# Feeder.net
KiCad netlist of a schematic drawn in Altium Designer
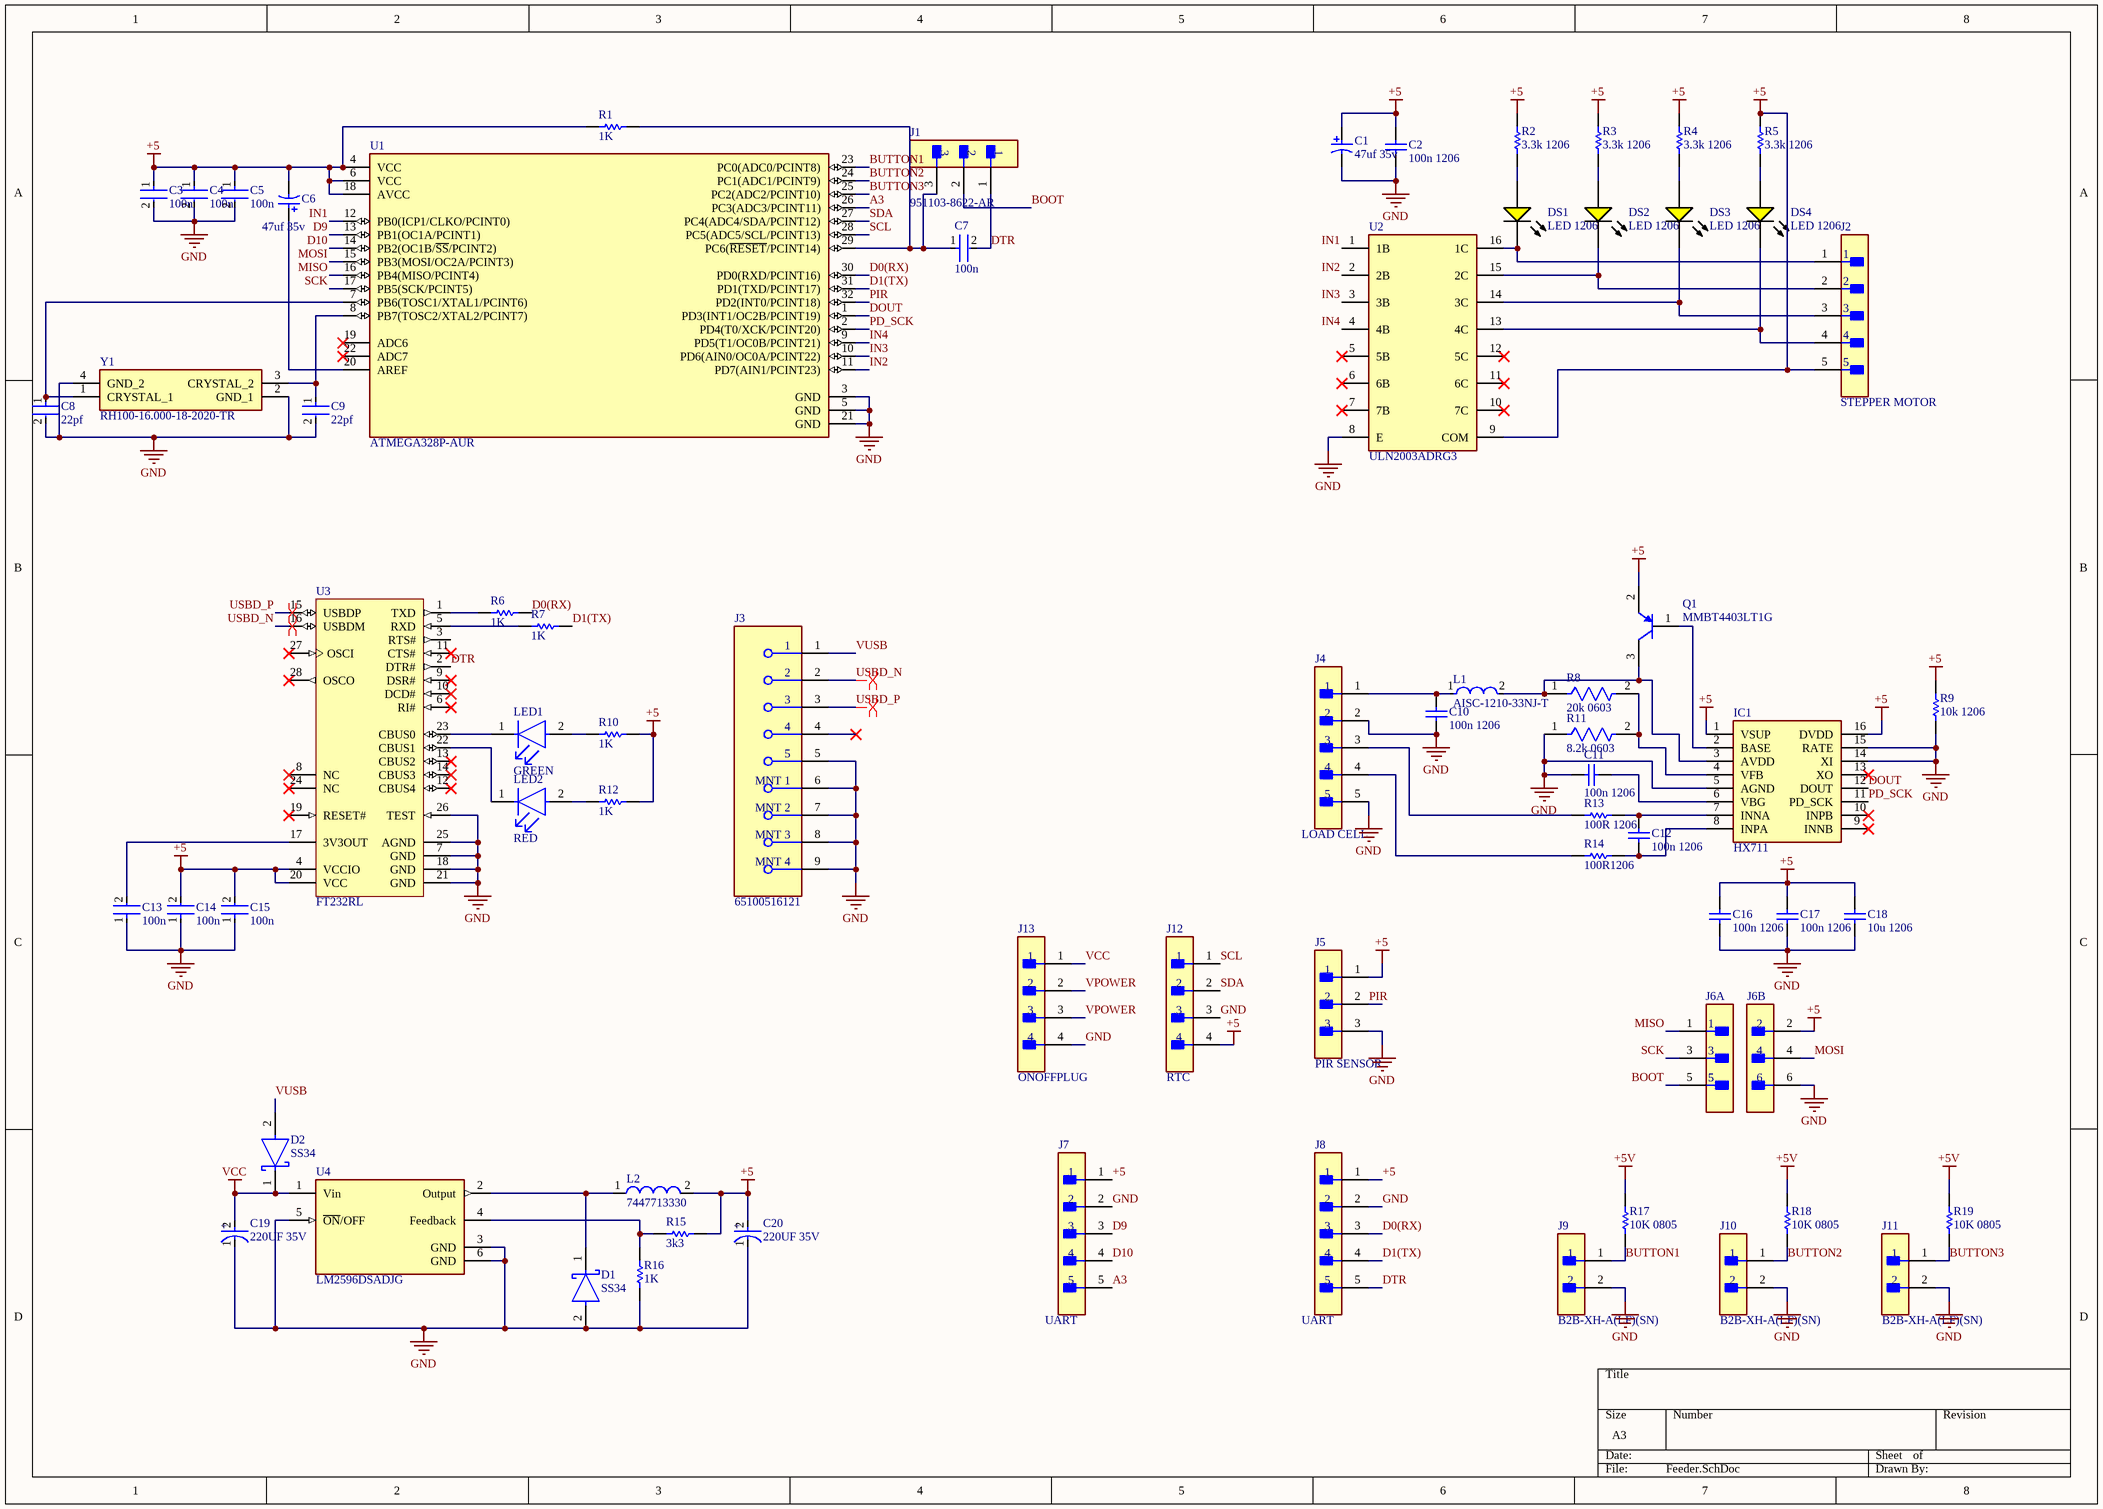
[diagram p0: Feeder.SchDoc]

(export (version "E")
  (design (tool "Eeschema 10.0.6"))
  (components
    (comp (ref "C1")
      (value "47uf 35v")
      (footprint "NIC-CAPA2-6.3X5.8_V")
      (fields (field (name "MANUFACTURER") "Nichicon") (field (name "PARTNUMBER") "UUD1V470MCL1GS"))
      (libsource (lib "Altium Content Vault") (part "NIC-CAP-P-2"))
    )
    (comp (ref "C2")
      (value "100n 1206")
      (footprint "CAPC3216X190X55ML30T25")
      (description "Chip Capacitor, 100 uF, +/- 20%, 6.3 V, -55 to 85 degC, 1206 (3216 Metric), RoHS, Tape and Reel")
      (fields (field (name "TOLERANCE") "20%") (field (name "PARTNUMBER") "GRM31CR60J107ME39L"))
      (libsource (lib "Altium Content Vault") (part "CAP-NP-2"))
    )
    (comp (ref "C3")
      (value "100n")
      (footprint "FP-C1206C-EB-MFG")
      (description "CAP CER 0.1UF 25V 5% NP0 1206")
      (fields
        (field (name "TOLERANCE") "0.05")
        (field (name "OCTOPART") "https://octopart.com/c1206c104j3gactu-kemet-9145095")
      )
      (libsource (lib "Altium Content Vault") (part "b4654b650e69147ec39a6b967a45e02"))
    )
    (comp (ref "C4")
      (value "100n")
      (footprint "FP-C1206C-EB-MFG")
      (description "CAP CER 0.1UF 25V 5% NP0 1206")
      (fields
        (field (name "TOLERANCE") "0.05")
        (field (name "OCTOPART") "https://octopart.com/c1206c104j3gactu-kemet-9145095")
      )
      (libsource (lib "Altium Content Vault") (part "b4654b650e69147ec39a6b967a45e02"))
    )
    (comp (ref "C5")
      (value "100n")
      (footprint "FP-C1206C-EB-MFG")
      (description "CAP CER 0.1UF 25V 5% NP0 1206")
      (fields
        (field (name "TOLERANCE") "0.05")
        (field (name "OCTOPART") "https://octopart.com/c1206c104j3gactu-kemet-9145095")
      )
      (libsource (lib "Altium Content Vault") (part "b4654b650e69147ec39a6b967a45e02"))
    )
    (comp (ref "C6")
      (value "47uf 35v")
      (footprint "NIC-CAPA2-6.3X5.8_V")
      (fields (field (name "MANUFACTURER") "Nichicon") (field (name "PARTNUMBER") "UUD1V470MCL1GS"))
      (libsource (lib "Altium Content Vault") (part "NIC-CAP-P-2"))
    )
    (comp (ref "C7")
      (value "100n")
      (footprint "FP-C1206C-EB-MFG")
      (description "CAP CER 0.1UF 25V 5% NP0 1206")
      (fields
        (field (name "TOLERANCE") "0.05")
        (field (name "OCTOPART") "https://octopart.com/c1206c104j3gactu-kemet-9145095")
      )
      (libsource (lib "Altium Content Vault") (part "b4654b650e69147ec39a6b967a45e02"))
    )
    (comp (ref "C8")
      (value "22pf")
      (footprint "FP-C1206C-EB-MFG")
      (description "1206 22pF Ceramic Multilayer Capacitor; 50VDC; 125degC; C0G Dielec; +/-5% SMD")
      (fields
        (field (name "OCTOPART") "https://octopart.com/c1206c220j5gactu-kemet-131912")
        (field (name "TOLERANCE") "0.05")
      )
      (libsource (lib "Altium Content Vault") (part "b4654b650e69147ec39a6b967a45e02"))
    )
    (comp (ref "C9")
      (value "22pf")
      (footprint "FP-C1206C-EB-MFG")
      (description "1206 22pF Ceramic Multilayer Capacitor; 50VDC; 125degC; C0G Dielec; +/-5% SMD")
      (fields
        (field (name "OCTOPART") "https://octopart.com/c1206c220j5gactu-kemet-131912")
        (field (name "TOLERANCE") "0.05")
      )
      (libsource (lib "Altium Content Vault") (part "b4654b650e69147ec39a6b967a45e02"))
    )
    (comp (ref "C10")
      (value "100n 1206")
      (footprint "CAPC3216X190X55ML30T25")
      (description "Chip Capacitor, 100 uF, +/- 20%, 6.3 V, -55 to 85 degC, 1206 (3216 Metric), RoHS, Tape and Reel")
      (fields (field (name "TOLERANCE") "20%") (field (name "PARTNUMBER") "GRM31CR60J107ME39L"))
      (libsource (lib "Altium Content Vault") (part "CAP-NP-2"))
    )
    (comp (ref "C11")
      (value "100n 1206")
      (footprint "CAPC3216X190X55ML30T25")
      (description "Chip Capacitor, 100 uF, +/- 20%, 6.3 V, -55 to 85 degC, 1206 (3216 Metric), RoHS, Tape and Reel")
      (fields (field (name "TOLERANCE") "20%") (field (name "PARTNUMBER") "GRM31CR60J107ME39L"))
      (libsource (lib "Altium Content Vault") (part "CAP-NP-2"))
    )
    (comp (ref "C12")
      (value "100n 1206")
      (footprint "CAPC3216X190X55ML30T25")
      (description "Chip Capacitor, 100 uF, +/- 20%, 6.3 V, -55 to 85 degC, 1206 (3216 Metric), RoHS, Tape and Reel")
      (fields (field (name "TOLERANCE") "20%") (field (name "PARTNUMBER") "GRM31CR60J107ME39L"))
      (libsource (lib "Altium Content Vault") (part "CAP-NP-2"))
    )
    (comp (ref "C13")
      (value "100n")
      (footprint "FP-C1206C-EB-MFG")
      (description "CAP CER 0.1UF 25V 5% NP0 1206")
      (fields
        (field (name "TOLERANCE") "0.05")
        (field (name "OCTOPART") "https://octopart.com/c1206c104j3gactu-kemet-9145095")
      )
      (libsource (lib "Altium Content Vault") (part "b4654b650e69147ec39a6b967a45e02"))
    )
    (comp (ref "C14")
      (value "100n")
      (footprint "FP-C1206C-EB-MFG")
      (description "CAP CER 0.1UF 25V 5% NP0 1206")
      (fields
        (field (name "TOLERANCE") "0.05")
        (field (name "OCTOPART") "https://octopart.com/c1206c104j3gactu-kemet-9145095")
      )
      (libsource (lib "Altium Content Vault") (part "b4654b650e69147ec39a6b967a45e02"))
    )
    (comp (ref "C15")
      (value "100n")
      (footprint "FP-C1206C-EB-MFG")
      (description "CAP CER 0.1UF 25V 5% NP0 1206")
      (fields
        (field (name "TOLERANCE") "0.05")
        (field (name "OCTOPART") "https://octopart.com/c1206c104j3gactu-kemet-9145095")
      )
      (libsource (lib "Altium Content Vault") (part "b4654b650e69147ec39a6b967a45e02"))
    )
    (comp (ref "C16")
      (value "100n 1206")
      (footprint "CAPC3216X190X55ML30T25")
      (description "Chip Capacitor, 100 uF, +/- 20%, 6.3 V, -55 to 85 degC, 1206 (3216 Metric), RoHS, Tape and Reel")
      (fields (field (name "TOLERANCE") "20%") (field (name "PARTNUMBER") "GRM31CR60J107ME39L"))
      (libsource (lib "Altium Content Vault") (part "CAP-NP-2"))
    )
    (comp (ref "C17")
      (value "100n 1206")
      (footprint "CAPC3216X190X55ML30T25")
      (description "Chip Capacitor, 100 uF, +/- 20%, 6.3 V, -55 to 85 degC, 1206 (3216 Metric), RoHS, Tape and Reel")
      (fields (field (name "TOLERANCE") "20%") (field (name "PARTNUMBER") "GRM31CR60J107ME39L"))
      (libsource (lib "Altium Content Vault") (part "CAP-NP-2"))
    )
    (comp (ref "C18")
      (value "10u 1206")
      (footprint "CAPC3216X190X55ML30T25")
      (description "Chip Capacitor, 10 uF, +/- 20%, 6.3 V, -55 to 85 degC, 1206 (3216 Metric), RoHS, Tape and Reel")
      (fields (field (name "TOLERANCE") "20%") (field (name "PARTNUMBER") "GRM31CR60J107ME39L"))
      (libsource (lib "Altium Content Vault") (part "CAP-NP-2"))
    )
    (comp (ref "C19")
      (value "220UF 35V")
      (footprint "FP-FC-G-MFG")
      (description "CAP ALUM 220UF 20% 35V SMD")
      (fields (field (name "TOLERANCE") "20%") (field (name "VOLTAGE") "35V"))
      (libsource (lib "Altium Content Vault") (part "8eef7423fb450d55d321f8a63fae760"))
    )
    (comp (ref "C20")
      (value "220UF 35V")
      (footprint "FP-FC-G-MFG")
      (description "CAP ALUM 220UF 20% 35V SMD")
      (fields (field (name "TOLERANCE") "20%") (field (name "VOLTAGE") "35V"))
      (libsource (lib "Altium Content Vault") (part "8eef7423fb450d55d321f8a63fae760"))
    )
    (comp (ref "D1")
      (value "SS34")
      (footprint "FP-SS34LWH-MFG")
      (description "DIODE SCHOTTKY 40V 3A SOD123W")
      (libsource (lib "Altium Content Vault") (part "1d6ec82d83fb6aee721767c19dac4b9"))
    )
    (comp (ref "D2")
      (value "SS34")
      (footprint "FP-SS34LWH-MFG")
      (description "DIODE SCHOTTKY 40V 3A SOD123W")
      (libsource (lib "Altium Content Vault") (part "1d6ec82d83fb6aee721767c19dac4b9"))
    )
    (comp (ref "DS1")
      (value "LED 1206")
      (footprint "LUMX-SML-LX1206YC-TR_V")
      (description "Yellow LED, Water Clear Len, 585 nm, 2.1 V, -40 to 85 degC, 2-Pin SMD, RoHS, Tape and Reel")
      (fields (field (name "MANUFACTURER") "Lumex"))
      (libsource (lib "Altium Content Vault") (part "LED-YELLOW-AK-2"))
    )
    (comp (ref "DS2")
      (value "LED 1206")
      (footprint "LUMX-SML-LX1206YC-TR_V")
      (description "Yellow LED, Water Clear Len, 585 nm, 2.1 V, -40 to 85 degC, 2-Pin SMD, RoHS, Tape and Reel")
      (fields (field (name "MANUFACTURER") "Lumex"))
      (libsource (lib "Altium Content Vault") (part "LED-YELLOW-AK-2"))
    )
    (comp (ref "DS3")
      (value "LED 1206")
      (footprint "LUMX-SML-LX1206YC-TR_V")
      (description "Yellow LED, Water Clear Len, 585 nm, 2.1 V, -40 to 85 degC, 2-Pin SMD, RoHS, Tape and Reel")
      (fields (field (name "MANUFACTURER") "Lumex"))
      (libsource (lib "Altium Content Vault") (part "LED-YELLOW-AK-2"))
    )
    (comp (ref "DS4")
      (value "LED 1206")
      (footprint "LUMX-SML-LX1206YC-TR_V")
      (description "Yellow LED, Water Clear Len, 585 nm, 2.1 V, -40 to 85 degC, 2-Pin SMD, RoHS, Tape and Reel")
      (fields (field (name "MANUFACTURER") "Lumex"))
      (libsource (lib "Altium Content Vault") (part "LED-YELLOW-AK-2"))
    )
    (comp (ref "IC1")
      (value "HX711")
      (footprint "SamacSys:SOIC127P600X160-16N")
      (description "Integrated Circuit")
      (libsource (lib "*") (part "HX711"))
    )
    (comp (ref "J1")
      (value "951103-8622-AR")
      (footprint "FP-951103-8622-AR-MFG")
      (description "CONN HEADER VERT 3POS 2MM")
      (fields
        (field (name "OCTOPART") "https://octopart.com/951103-8622-ar-3m-14400669")
        (field (name "MANUFACTURER") "3M")
      )
      (libsource (lib "Altium Content Vault") (part "0d3f023dd272f625e17a2be33dea85f"))
    )
    (comp (ref "J2")
      (value "STEPPER MOTOR")
      (footprint "FP-B5B-XH-AM_LF_SN-MFG")
      (description "CONN HEADER VERT 5POS 2.5MM B5B-XH-AM(LF)(SN)")
      (libsource (lib "") (part "bf93c07fd2649a848d0ec8585582aab_1"))
    )
    (comp (ref "J3")
      (value "65100516121")
      (footprint "FP-65100516121-MFG")
      (description "CONN RCPT USB2.0 MINI B SMD R/A")
      (libsource (lib "Altium Content Vault") (part "ef2d7afec5ba4af7dc5ac0a08bf6999"))
    )
    (comp (ref "J4")
      (value "LOAD CELL")
      (footprint "FP-B5B-XH-AM_LF_SN-MFG")
      (description "CONN HEADER VERT 5POS 2.5MM B5B-XH-AM(LF)(SN)")
      (libsource (lib "Altium Content Vault") (part "bf93c07fd2649a848d0ec8585582aab"))
    )
    (comp (ref "J5")
      (value "PIR SENSOR")
      (footprint "FP-B3B-XH-A_LF_SN-MFG")
      (description "CONN HEADER VERT 3POS 2.5MM")
      (libsource (lib "") (part "0d3f023dd272f625e17a2be33dea85f_1"))
    )
    (comp (ref "J6")
      (value "~")
      (footprint "FP-90130-1206-MFG")
      (description "CONN HEADER VERT 6POS 2.54MM")
      (libsource (lib "Altium Content Vault") (part "2654a11fb13586ecb194516b1c997bc"))
    )
    (comp (ref "J7")
      (value "UART")
      (footprint "FP-B5B-XH-AM_LF_SN-MFG")
      (description "CONN HEADER VERT 5POS 2.5MM B5B-XH-AM(LF)(SN)")
      (libsource (lib "Altium Content Vault") (part "bf93c07fd2649a848d0ec8585582aab"))
    )
    (comp (ref "J8")
      (value "UART")
      (footprint "FP-B5B-XH-AM_LF_SN-MFG")
      (description "CONN HEADER VERT 5POS 2.5MM B5B-XH-AM(LF)(SN)")
      (libsource (lib "Altium Content Vault") (part "bf93c07fd2649a848d0ec8585582aab"))
    )
    (comp (ref "J9")
      (value "B2B-XH-A(LF)(SN)")
      (footprint "FP-B2B-XH-A_LF_SN-MFG")
      (description "CONN HEADER VERT 2POS 2.5MM")
      (libsource (lib "Altium Content Vault") (part "3bc925449376181038e59eaffc5286c"))
    )
    (comp (ref "J10")
      (value "B2B-XH-A(LF)(SN)")
      (footprint "FP-B2B-XH-A_LF_SN-MFG")
      (description "CONN HEADER VERT 2POS 2.5MM")
      (libsource (lib "Altium Content Vault") (part "3bc925449376181038e59eaffc5286c"))
    )
    (comp (ref "J11")
      (value "B2B-XH-A(LF)(SN)")
      (footprint "FP-B2B-XH-A_LF_SN-MFG")
      (description "CONN HEADER VERT 2POS 2.5MM")
      (libsource (lib "Altium Content Vault") (part "3bc925449376181038e59eaffc5286c"))
    )
    (comp (ref "J12")
      (value "RTC")
      (footprint "FP-B4B-XH-A_LF_SN-MFG")
      (description "CONN HEADER VERT 4POS 2.5MM")
      (libsource (lib "Altium Content Vault") (part "299a8cea1bdcbc3624fe62c390fa72c"))
    )
    (comp (ref "J13")
      (value "ONOFFPLUG")
      (footprint "FP-B4B-XH-A_LF_SN-MFG")
      (description "CONN HEADER VERT 4POS 2.5MM")
      (libsource (lib "Altium Content Vault") (part "299a8cea1bdcbc3624fe62c390fa72c"))
    )
    (comp (ref "L1")
      (value "AISC-1210-33NJ-T")
      (footprint "FP-AISC-1210-MFG")
      (description "Unshielded Wirewound Inductor 33nH 5% 1000mA 0.11Ω SMD")
      (fields (field (name "TOLERANCE") "5%"))
      (libsource (lib "Altium Content Vault") (part "725321dda6339637d4d059423bc1c3c"))
    )
    (comp (ref "L2")
      (value "7447713330")
      (footprint "WE-PD 1030")
      (description "SMD-Shielded Power Inductor WE-PD, L=33.0 µH")
      (fields (field (name "MANUFACTURER") "Wuerth Elektronik"))
      (libsource (lib "Altium Content Vault") (part "PAS-IND-INDUCTOR-2"))
    )
    (comp (ref "LED1")
      (value "GREEN")
      (footprint "FP-150120GS75000-MFG")
      (description "LED GREEN CLEAR 1206 SMD")
      (libsource (lib "Altium Content Vault") (part "8706943c75ba83719d021d2fdc84c58"))
    )
    (comp (ref "LED2")
      (value "RED")
      (footprint "FP-150120GS75000-MFG")
      (description "LED GREEN CLEAR 1206 SMD")
      (libsource (lib "Altium Content Vault") (part "8706943c75ba83719d021d2fdc84c58"))
    )
    (comp (ref "Q1")
      (value "MMBT4403LT1G")
      (footprint "ONSC-SOT-23-3-318-08_V")
      (description "Switching Transistor, PNP Silicon, 3-Pin SOT-23, Pb-Free, Tape and Reel")
      (fields (field (name "MANUFACTURER") "On Semiconductor"))
      (libsource (lib "Altium Content Vault") (part "ONSC-PNP-B1E2C3-3"))
    )
    (comp (ref "R1")
      (value "1K")
      (footprint "RESC3216X70X50LL05T20")
      (fields (field (name "MANUFACTURER") "Panasonic") (field (name "PART NUMBER") "ERJ-8ENF1001V"))
      (libsource (lib "Altium Content Vault") (part "RES"))
    )
    (comp (ref "R2")
      (value "3.3k 1206")
      (footprint "RESC3116X65X40ML10T20")
      (description "Chip Resistor, 3.3 KOhm, +/- 1%, 0.25 W, -55 to 155 degC, 1206 (3216 Metric), RoHS, Tape and Reel")
      (fields (field (name "TOLERANCE") "1%") (field (name "MANUFACTURER") "Yageo"))
      (libsource (lib "Altium Content Vault") (part "RES-2"))
    )
    (comp (ref "R3")
      (value "3.3k 1206")
      (footprint "RESC3116X65X40ML10T20")
      (description "Chip Resistor, 3.3 KOhm, +/- 1%, 0.25 W, -55 to 155 degC, 1206 (3216 Metric), RoHS, Tape and Reel")
      (fields (field (name "TOLERANCE") "1%") (field (name "MANUFACTURER") "Yageo"))
      (libsource (lib "Altium Content Vault") (part "RES-2"))
    )
    (comp (ref "R4")
      (value "3.3k 1206")
      (footprint "RESC3116X65X40ML10T20")
      (description "Chip Resistor, 3.3 KOhm, +/- 1%, 0.25 W, -55 to 155 degC, 1206 (3216 Metric), RoHS, Tape and Reel")
      (fields (field (name "TOLERANCE") "1%") (field (name "MANUFACTURER") "Yageo"))
      (libsource (lib "Altium Content Vault") (part "RES-2"))
    )
    (comp (ref "R5")
      (value "3.3k 1206")
      (footprint "RESC3116X65X40ML10T20")
      (description "Chip Resistor, 3.3 KOhm, +/- 1%, 0.25 W, -55 to 155 degC, 1206 (3216 Metric), RoHS, Tape and Reel")
      (fields (field (name "TOLERANCE") "1%") (field (name "MANUFACTURER") "Yageo"))
      (libsource (lib "Altium Content Vault") (part "RES-2"))
    )
    (comp (ref "R6")
      (value "1K")
      (footprint "RESC3216X70X50LL05T20")
      (fields (field (name "MANUFACTURER") "Panasonic") (field (name "PART NUMBER") "ERJ-8ENF1001V"))
      (libsource (lib "Altium Content Vault") (part "RES"))
    )
    (comp (ref "R7")
      (value "1K")
      (footprint "RESC3216X70X50LL05T20")
      (fields (field (name "MANUFACTURER") "Panasonic") (field (name "PART NUMBER") "ERJ-8ENF1001V"))
      (libsource (lib "Altium Content Vault") (part "RES"))
    )
    (comp (ref "R8")
      (value "20k 0603")
      (footprint "FP-RC0603-0_55-IPC_C")
      (description "RES 20kK OHM 1% 1/10W 0603")
      (fields (field (name "TOLERANCE") "1%"))
      (libsource (lib "Altium Content Vault") (part "1029c3af85768c4190bb7ad29bc67b5"))
    )
    (comp (ref "R9")
      (value "10k 1206")
      (footprint "RESC3116X65X40ML10T20")
      (description "Chip Resistor, 10 KOhm, +/- 1%, 0.25 W, -55 to 155 degC, 1206 (3216 Metric), RoHS, Tape and Reel")
      (fields (field (name "TOLERANCE") "1%") (field (name "MANUFACTURER") "Yageo"))
      (libsource (lib "Altium Content Vault") (part "RES-2"))
    )
    (comp (ref "R10")
      (value "1K")
      (footprint "RESC3216X70X50LL05T20")
      (fields (field (name "MANUFACTURER") "Panasonic") (field (name "PART NUMBER") "ERJ-8ENF1001V"))
      (libsource (lib "Altium Content Vault") (part "RES"))
    )
    (comp (ref "R11")
      (value "8.2k 0603")
      (footprint "FP-RC0603-0_55-IPC_C")
      (description "RES 8.2K OHM 1% 1/10W 0603")
      (fields (field (name "TOLERANCE") "1%"))
      (libsource (lib "Altium Content Vault") (part "1029c3af85768c4190bb7ad29bc67b5"))
    )
    (comp (ref "R12")
      (value "1K")
      (footprint "RESC3216X70X50LL05T20")
      (fields (field (name "MANUFACTURER") "Panasonic") (field (name "PART NUMBER") "ERJ-8ENF1001V"))
      (libsource (lib "Altium Content Vault") (part "RES"))
    )
    (comp (ref "R13")
      (value "100R 1206")
      (footprint "RESC3116X65X40ML10T20")
      (description "Chip Resistor, 100 Ohm, +/- 1%, 0.25 W, -55 to 155 degC, 1206 (3216 Metric), RoHS, Tape and Reel")
      (fields (field (name "MANUFACTURER") "Yageo") (field (name "TOLERANCE") "1%"))
      (libsource (lib "Altium Content Vault") (part "RES-2"))
    )
    (comp (ref "R14")
      (value "100R1206")
      (footprint "RESC3116X65X40ML10T20")
      (description "Chip Resistor, 100 Ohm, +/- 1%, 0.25 W, -55 to 155 degC, 1206 (3216 Metric), RoHS, Tape and Reel")
      (fields (field (name "MANUFACTURER") "Yageo") (field (name "TOLERANCE") "1%"))
      (libsource (lib "Altium Content Vault") (part "RES-2"))
    )
    (comp (ref "R15")
      (value "3k3")
      (footprint "RESC3216X70X50LL05T20")
      (fields (field (name "MANUFACTURER") "Panasonic") (field (name "PART NUMBER") "ERJ-8ENF1001V"))
      (libsource (lib "Altium Content Vault") (part "RES"))
    )
    (comp (ref "R16")
      (value "1K")
      (footprint "RESC3216X70X50LL05T20")
      (fields (field (name "MANUFACTURER") "Panasonic") (field (name "PART NUMBER") "ERJ-8ENF1001V"))
      (libsource (lib "Altium Content Vault") (part "RES"))
    )
    (comp (ref "R17")
      (value "10K 0805")
      (footprint "RESC2013X60X35NL10T20")
      (description "Chip Resistor, 10 KOhm, +/- 1%, 0.125 W, -55 to 155 degC, 0805 (2012 Metric), RoHS, Tape and Reel")
      (fields (field (name "MANUFACTURER") "Yageo"))
      (libsource (lib "Altium Content Vault") (part "RES-2"))
    )
    (comp (ref "R18")
      (value "10K 0805")
      (footprint "RESC2013X60X35NL10T20")
      (description "Chip Resistor, 10 KOhm, +/- 1%, 0.125 W, -55 to 155 degC, 0805 (2012 Metric), RoHS, Tape and Reel")
      (fields (field (name "MANUFACTURER") "Yageo"))
      (libsource (lib "Altium Content Vault") (part "RES-2"))
    )
    (comp (ref "R19")
      (value "10K 0805")
      (footprint "RESC2013X60X35NL10T20")
      (description "Chip Resistor, 10 KOhm, +/- 1%, 0.125 W, -55 to 155 degC, 0805 (2012 Metric), RoHS, Tape and Reel")
      (fields (field (name "MANUFACTURER") "Yageo"))
      (libsource (lib "Altium Content Vault") (part "RES-2"))
    )
    (comp (ref "U1")
      (value "ATMEGA328P-AUR")
      (footprint "FP-32A-IPC_C")
      (description "IC MCU 8BIT 32KB FLASH 32TQFP")
      (libsource (lib "Altium Content Vault") (part "a21e5c44209584805972c9959ca5560"))
    )
    (comp (ref "U2")
      (value "ULN2003ADRG3")
      (footprint "FP-D0016A-IPC_A")
      (description "TRANS 7NPN DARL 50V 0.5A 16SOIC")
      (libsource (lib "Altium Content Vault") (part "f184887cc540b3f78e4f3a3a2a9e72d"))
    )
    (comp (ref "U3")
      (value "FT232RL")
      (footprint "FTDI-SSOP-28_M")
      (description "IC USB FS SERIAL UART 28-SSOP")
      (fields (field (name "MANUFACTURER") "FTDI"))
      (libsource (lib "Altium Content Vault") (part "FTDI-FT232-SSOP-28"))
    )
    (comp (ref "U4")
      (value "LM2596DSADJG")
      (footprint "FP-936A-02-MFG")
      (description "IC REG MULT CONFG ADJ 3A D2PAK-5")
      (fields
        (field (name "OCTOPART") "https://octopart.com/lm2596dsadjg-on+semiconductor-12437034")
        (field (name "MANUFACTURER") "ON Semiconductor")
      )
      (libsource (lib "Altium Content Vault") (part "6e009c68f80b765d55aa2e30e527964"))
    )
    (comp (ref "Y1")
      (value "RH100-16.000-18-2020-TR")
      (footprint "SamacSys:RH10012000182020TR")
      (description "Crystal or Oscillator")
      (fields (field (name "MANUFACTURER_PART_NUMBER") "RH100-12.000-18-2020-TR"))
      (libsource (lib "*") (part "RH100-12.000-18-2020-TR"))
    )
  )
  (nets
    (net (code "1") (name "+5") (class "Default")
      (node (ref "C1") (pin "1") (pinfunction "1_1") (pintype "passive"))
      (node (ref "C14") (pin "2") (pinfunction "2_2") (pintype "passive"))
      (node (ref "C15") (pin "2") (pinfunction "2_2") (pintype "passive"))
      (node (ref "C16") (pin "2") (pinfunction "2_2") (pintype "passive"))
      (node (ref "C17") (pin "2") (pinfunction "2_2") (pintype "passive"))
      (node (ref "C18") (pin "2") (pinfunction "2_2") (pintype "passive"))
      (node (ref "C2") (pin "2") (pinfunction "2_2") (pintype "passive"))
      (node (ref "C20") (pin "2") (pinfunction "A_2") (pintype "passive"))
      (node (ref "C3") (pin "1") (pinfunction "1_1") (pintype "passive"))
      (node (ref "C4") (pin "1") (pinfunction "1_1") (pintype "passive"))
      (node (ref "C5") (pin "1") (pinfunction "1_1") (pintype "passive"))
      (node (ref "C6") (pin "2") (pinfunction "2_2") (pintype "passive"))
      (node (ref "IC1") (pin "1") (pinfunction "VSUP_1") (pintype "passive"))
      (node (ref "IC1") (pin "16") (pinfunction "DVDD_16") (pintype "passive"))
      (node (ref "J12") (pin "4") (pinfunction "4_4") (pintype "passive"))
      (node (ref "J2") (pin "5") (pinfunction "5_5") (pintype "passive"))
      (node (ref "J5") (pin "1") (pinfunction "1_1") (pintype "passive"))
      (node (ref "J6") (pin "2") (pinfunction "2_2") (pintype "passive"))
      (node (ref "J7") (pin "1") (pinfunction "1_1") (pintype "passive"))
      (node (ref "J8") (pin "1") (pinfunction "1_1") (pintype "passive"))
      (node (ref "L2") (pin "2") (pinfunction "2_2") (pintype "passive"))
      (node (ref "Q1") (pin "2") (pinfunction "E_2") (pintype "passive"))
      (node (ref "R1") (pin "1") (pinfunction "1_1") (pintype "passive"))
      (node (ref "R10") (pin "2") (pinfunction "2_2") (pintype "passive"))
      (node (ref "R12") (pin "2") (pinfunction "2_2") (pintype "passive"))
      (node (ref "R15") (pin "2") (pinfunction "2_2") (pintype "passive"))
      (node (ref "R2") (pin "2") (pinfunction "2_2") (pintype "passive"))
      (node (ref "R3") (pin "2") (pinfunction "2_2") (pintype "passive"))
      (node (ref "R4") (pin "2") (pinfunction "2_2") (pintype "passive"))
      (node (ref "R5") (pin "2") (pinfunction "2_2") (pintype "passive"))
      (node (ref "R9") (pin "2") (pinfunction "2_2") (pintype "passive"))
      (node (ref "U1") (pin "18") (pinfunction "AVCC_18") (pintype "power_in"))
      (node (ref "U1") (pin "4") (pinfunction "VCC_4") (pintype "power_in"))
      (node (ref "U1") (pin "6") (pinfunction "VCC_6") (pintype "power_in"))
      (node (ref "U2") (pin "9") (pinfunction "COM_9") (pintype "passive"))
      (node (ref "U3") (pin "20") (pinfunction "VCC_20") (pintype "power_in"))
      (node (ref "U3") (pin "4") (pinfunction "VCCIO_4") (pintype "power_in"))
    )
    (net (code "2") (name "+5V") (class "Default")
      (node (ref "R17") (pin "2") (pinfunction "2_2") (pintype "passive"))
      (node (ref "R18") (pin "2") (pinfunction "2_2") (pintype "passive"))
      (node (ref "R19") (pin "2") (pinfunction "2_2") (pintype "passive"))
    )
    (net (code "3") (name "/A3") (class "Default")
      (node (ref "J7") (pin "5") (pinfunction "5_5") (pintype "passive"))
      (node (ref "U1") (pin "26") (pinfunction "PC3(ADC3/PCINT11)_26") (pintype "bidirectional"))
    )
    (net (code "4") (name "/BOOT") (class "Default")
      (node (ref "J1") (pin "2") (pinfunction "2_2") (pintype "passive"))
      (node (ref "J6") (pin "5") (pinfunction "5_5") (pintype "passive"))
    )
    (net (code "5") (name "/BUTTON1") (class "Default")
      (node (ref "J9") (pin "1") (pinfunction "1_1") (pintype "passive"))
      (node (ref "R17") (pin "1") (pinfunction "1_1") (pintype "passive"))
      (node (ref "U1") (pin "23") (pinfunction "PC0(ADC0/PCINT8)_23") (pintype "bidirectional"))
    )
    (net (code "6") (name "/BUTTON2") (class "Default")
      (node (ref "J10") (pin "1") (pinfunction "1_1") (pintype "passive"))
      (node (ref "R18") (pin "1") (pinfunction "1_1") (pintype "passive"))
      (node (ref "U1") (pin "24") (pinfunction "PC1(ADC1/PCINT9)_24") (pintype "bidirectional"))
    )
    (net (code "7") (name "/BUTTON3") (class "Default")
      (node (ref "J11") (pin "1") (pinfunction "1_1") (pintype "passive"))
      (node (ref "R19") (pin "1") (pinfunction "1_1") (pintype "passive"))
      (node (ref "U1") (pin "25") (pinfunction "PC2(ADC2/PCINT10)_25") (pintype "bidirectional"))
    )
    (net (code "8") (name "/D0(RX)") (class "Default")
      (node (ref "J8") (pin "3") (pinfunction "3_3") (pintype "passive"))
      (node (ref "R6") (pin "2") (pinfunction "2_2") (pintype "passive"))
      (node (ref "U1") (pin "30") (pinfunction "PD0(RXD/PCINT16)_30") (pintype "bidirectional"))
    )
    (net (code "9") (name "/D1(TX)") (class "Default")
      (node (ref "J8") (pin "4") (pinfunction "4_4") (pintype "passive"))
      (node (ref "R7") (pin "2") (pinfunction "2_2") (pintype "passive"))
      (node (ref "U1") (pin "31") (pinfunction "PD1(TXD/PCINT17)_31") (pintype "bidirectional"))
    )
    (net (code "10") (name "/D9") (class "Default")
      (node (ref "J7") (pin "3") (pinfunction "3_3") (pintype "passive"))
      (node (ref "U1") (pin "13") (pinfunction "PB1(OC1A/PCINT1)_13") (pintype "bidirectional"))
    )
    (net (code "11") (name "/D10") (class "Default")
      (node (ref "J7") (pin "4") (pinfunction "4_4") (pintype "passive"))
      (node (ref "U1") (pin "14") (pinfunction "PB2(OC1B/~{SS}/PCINT2)_14") (pintype "bidirectional"))
    )
    (net (code "12") (name "/DOUT") (class "Default")
      (node (ref "IC1") (pin "12") (pinfunction "DOUT_12") (pintype "passive"))
      (node (ref "U1") (pin "1") (pinfunction "PD3(INT1/OC2B/PCINT19)_1") (pintype "bidirectional"))
    )
    (net (code "13") (name "/DTR") (class "Default")
      (node (ref "C7") (pin "2") (pinfunction "2_2") (pintype "passive"))
      (node (ref "J1") (pin "1") (pinfunction "1_1") (pintype "passive"))
      (node (ref "J8") (pin "5") (pinfunction "5_5") (pintype "passive"))
      (node (ref "U3") (pin "2") (pinfunction "DTR#_2") (pintype "output"))
    )
    (net (code "14") (name "/IN1") (class "Default")
      (node (ref "U1") (pin "12") (pinfunction "PB0(ICP1/CLKO/PCINT0)_12") (pintype "bidirectional"))
      (node (ref "U2") (pin "1") (pinfunction "1B_1") (pintype "passive"))
    )
    (net (code "15") (name "/IN2") (class "Default")
      (node (ref "U1") (pin "11") (pinfunction "PD7(AIN1/PCINT23)_11") (pintype "bidirectional"))
      (node (ref "U2") (pin "2") (pinfunction "2B_2") (pintype "passive"))
    )
    (net (code "16") (name "/IN3") (class "Default")
      (node (ref "U1") (pin "10") (pinfunction "PD6(AIN0/OC0A/PCINT22)_10") (pintype "bidirectional"))
      (node (ref "U2") (pin "3") (pinfunction "3B_3") (pintype "passive"))
    )
    (net (code "17") (name "/IN4") (class "Default")
      (node (ref "U1") (pin "9") (pinfunction "PD5(T1/OC0B/PCINT21)_9") (pintype "bidirectional"))
      (node (ref "U2") (pin "4") (pinfunction "4B_4") (pintype "passive"))
    )
    (net (code "18") (name "/MISO") (class "Default")
      (node (ref "J6") (pin "1") (pinfunction "1_1") (pintype "passive"))
      (node (ref "U1") (pin "16") (pinfunction "PB4(MISO/PCINT4)_16") (pintype "bidirectional"))
    )
    (net (code "19") (name "/MOSI") (class "Default")
      (node (ref "J6") (pin "4") (pinfunction "4_4") (pintype "passive"))
      (node (ref "U1") (pin "15") (pinfunction "PB3(MOSI/OC2A/PCINT3)_15") (pintype "bidirectional"))
    )
    (net (code "20") (name "/PD_SCK") (class "Default")
      (node (ref "IC1") (pin "11") (pinfunction "PD_SCK_11") (pintype "passive"))
      (node (ref "U1") (pin "2") (pinfunction "PD4(T0/XCK/PCINT20)_2") (pintype "bidirectional"))
    )
    (net (code "21") (name "/PIR") (class "Default")
      (node (ref "J5") (pin "2") (pinfunction "2_2") (pintype "passive"))
      (node (ref "U1") (pin "32") (pinfunction "PD2(INT0/PCINT18)_32") (pintype "bidirectional"))
    )
    (net (code "22") (name "/SCK") (class "Default")
      (node (ref "J6") (pin "3") (pinfunction "3_3") (pintype "passive"))
      (node (ref "U1") (pin "17") (pinfunction "PB5(SCK/PCINT5)_17") (pintype "bidirectional"))
    )
    (net (code "23") (name "/SCL") (class "Default")
      (node (ref "J12") (pin "1") (pinfunction "1_1") (pintype "passive"))
      (node (ref "U1") (pin "28") (pinfunction "PC5(ADC5/SCL/PCINT13)_28") (pintype "bidirectional"))
    )
    (net (code "24") (name "/SDA") (class "Default")
      (node (ref "J12") (pin "2") (pinfunction "2_2") (pintype "passive"))
      (node (ref "U1") (pin "27") (pinfunction "PC4(ADC4/SDA/PCINT12)_27") (pintype "bidirectional"))
    )
    (net (code "25") (name "/USBD_N") (class "Default")
      (node (ref "J3") (pin "2") (pinfunction "2_2") (pintype "passive"))
      (node (ref "U3") (pin "16") (pinfunction "USBDM_16") (pintype "bidirectional"))
    )
    (net (code "26") (name "/USBD_P") (class "Default")
      (node (ref "J3") (pin "3") (pinfunction "3_3") (pintype "passive"))
      (node (ref "U3") (pin "15") (pinfunction "USBDP_15") (pintype "bidirectional"))
    )
    (net (code "27") (name "/VPOWER") (class "Default")
      (node (ref "J13") (pin "2") (pinfunction "2_2") (pintype "passive"))
      (node (ref "J13") (pin "3") (pinfunction "3_3") (pintype "passive"))
    )
    (net (code "28") (name "/VUSB") (class "Default")
      (node (ref "D2") (pin "2") (pinfunction "A_2") (pintype "passive"))
      (node (ref "J3") (pin "1") (pinfunction "1_1") (pintype "passive"))
    )
    (net (code "29") (name "GND") (class "Default")
      (node (ref "C1") (pin "2") (pinfunction "2_2") (pintype "passive"))
      (node (ref "C10") (pin "1") (pinfunction "1_1") (pintype "passive"))
      (node (ref "C11") (pin "2") (pinfunction "2_2") (pintype "passive"))
      (node (ref "C13") (pin "1") (pinfunction "1_1") (pintype "passive"))
      (node (ref "C14") (pin "1") (pinfunction "1_1") (pintype "passive"))
      (node (ref "C15") (pin "1") (pinfunction "1_1") (pintype "passive"))
      (node (ref "C16") (pin "1") (pinfunction "1_1") (pintype "passive"))
      (node (ref "C17") (pin "1") (pinfunction "1_1") (pintype "passive"))
      (node (ref "C18") (pin "1") (pinfunction "1_1") (pintype "passive"))
      (node (ref "C19") (pin "1") (pinfunction "C_1") (pintype "passive"))
      (node (ref "C2") (pin "1") (pinfunction "1_1") (pintype "passive"))
      (node (ref "C20") (pin "1") (pinfunction "C_1") (pintype "passive"))
      (node (ref "C3") (pin "2") (pinfunction "2_2") (pintype "passive"))
      (node (ref "C4") (pin "2") (pinfunction "2_2") (pintype "passive"))
      (node (ref "C5") (pin "2") (pinfunction "2_2") (pintype "passive"))
      (node (ref "C8") (pin "2") (pinfunction "2_2") (pintype "passive"))
      (node (ref "C9") (pin "2") (pinfunction "2_2") (pintype "passive"))
      (node (ref "D1") (pin "2") (pinfunction "A_2") (pintype "passive"))
      (node (ref "IC1") (pin "14") (pinfunction "XI_14") (pintype "passive"))
      (node (ref "IC1") (pin "15") (pinfunction "RATE_15") (pintype "passive"))
      (node (ref "IC1") (pin "5") (pinfunction "AGND_5") (pintype "passive"))
      (node (ref "J10") (pin "2") (pinfunction "2_2") (pintype "passive"))
      (node (ref "J11") (pin "2") (pinfunction "2_2") (pintype "passive"))
      (node (ref "J12") (pin "3") (pinfunction "3_3") (pintype "passive"))
      (node (ref "J13") (pin "4") (pinfunction "4_4") (pintype "passive"))
      (node (ref "J3") (pin "5") (pinfunction "5_5") (pintype "passive"))
      (node (ref "J3") (pin "6") (pinfunction "MNT_1_6") (pintype "passive"))
      (node (ref "J3") (pin "7") (pinfunction "MNT_2_7") (pintype "passive"))
      (node (ref "J3") (pin "8") (pinfunction "MNT_3_8") (pintype "passive"))
      (node (ref "J3") (pin "9") (pinfunction "MNT_4_9") (pintype "passive"))
      (node (ref "J4") (pin "2") (pinfunction "2_2") (pintype "passive"))
      (node (ref "J4") (pin "5") (pinfunction "5_5") (pintype "passive"))
      (node (ref "J5") (pin "3") (pinfunction "3_3") (pintype "passive"))
      (node (ref "J6") (pin "6") (pinfunction "6_6") (pintype "passive"))
      (node (ref "J7") (pin "2") (pinfunction "2_2") (pintype "passive"))
      (node (ref "J8") (pin "2") (pinfunction "2_2") (pintype "passive"))
      (node (ref "J9") (pin "2") (pinfunction "2_2") (pintype "passive"))
      (node (ref "R11") (pin "1") (pinfunction "1_1") (pintype "passive"))
      (node (ref "R16") (pin "1") (pinfunction "1_1") (pintype "passive"))
      (node (ref "R9") (pin "1") (pinfunction "1_1") (pintype "passive"))
      (node (ref "U1") (pin "21") (pinfunction "GND_21") (pintype "power_in"))
      (node (ref "U1") (pin "3") (pinfunction "GND_3") (pintype "power_in"))
      (node (ref "U1") (pin "5") (pinfunction "GND_5") (pintype "power_in"))
      (node (ref "U2") (pin "8") (pinfunction "E_8") (pintype "passive"))
      (node (ref "U3") (pin "18") (pinfunction "GND_18") (pintype "power_in"))
      (node (ref "U3") (pin "21") (pinfunction "GND_21") (pintype "power_in"))
      (node (ref "U3") (pin "25") (pinfunction "AGND_25") (pintype "power_in"))
      (node (ref "U3") (pin "26") (pinfunction "TEST_26") (pintype "input"))
      (node (ref "U3") (pin "7") (pinfunction "GND_7") (pintype "power_in"))
      (node (ref "U4") (pin "3") (pinfunction "GND_3") (pintype "power_in"))
      (node (ref "U4") (pin "5") (pinfunction "~{ON}/OFF_5") (pintype "input"))
      (node (ref "U4") (pin "6") (pinfunction "GND_6") (pintype "power_in"))
      (node (ref "Y1") (pin "2") (pinfunction "GND_1_2") (pintype "passive"))
      (node (ref "Y1") (pin "4") (pinfunction "GND_2_4") (pintype "passive"))
    )
    (net (code "30") (name "Net-(C10-Pad2)") (class "Default")
      (node (ref "C10") (pin "2") (pinfunction "2_2") (pintype "passive"))
      (node (ref "J4") (pin "1") (pinfunction "1_1") (pintype "passive"))
      (node (ref "L1") (pin "1") (pinfunction "1_1") (pintype "passive"))
    )
    (net (code "31") (name "Net-(D1-C)") (class "Default")
      (node (ref "D1") (pin "1") (pinfunction "C_1") (pintype "passive"))
      (node (ref "L2") (pin "1") (pinfunction "1_1") (pintype "passive"))
      (node (ref "U4") (pin "2") (pinfunction "Output_2") (pintype "output"))
    )
    (net (code "32") (name "Net-(DS1-A)") (class "Default")
      (node (ref "DS1") (pin "1") (pinfunction "A_1") (pintype "passive"))
      (node (ref "R2") (pin "1") (pinfunction "1_1") (pintype "passive"))
    )
    (net (code "33") (name "Net-(DS1-K)") (class "Default")
      (node (ref "DS1") (pin "2") (pinfunction "K_2") (pintype "passive"))
      (node (ref "J2") (pin "1") (pinfunction "1_1") (pintype "passive"))
      (node (ref "U2") (pin "16") (pinfunction "1C_16") (pintype "passive"))
    )
    (net (code "34") (name "Net-(DS2-A)") (class "Default")
      (node (ref "DS2") (pin "1") (pinfunction "A_1") (pintype "passive"))
      (node (ref "R3") (pin "1") (pinfunction "1_1") (pintype "passive"))
    )
    (net (code "35") (name "Net-(DS2-K)") (class "Default")
      (node (ref "DS2") (pin "2") (pinfunction "K_2") (pintype "passive"))
      (node (ref "J2") (pin "2") (pinfunction "2_2") (pintype "passive"))
      (node (ref "U2") (pin "15") (pinfunction "2C_15") (pintype "passive"))
    )
    (net (code "36") (name "Net-(DS3-A)") (class "Default")
      (node (ref "DS3") (pin "1") (pinfunction "A_1") (pintype "passive"))
      (node (ref "R4") (pin "1") (pinfunction "1_1") (pintype "passive"))
    )
    (net (code "37") (name "Net-(DS3-K)") (class "Default")
      (node (ref "DS3") (pin "2") (pinfunction "K_2") (pintype "passive"))
      (node (ref "J2") (pin "3") (pinfunction "3_3") (pintype "passive"))
      (node (ref "U2") (pin "14") (pinfunction "3C_14") (pintype "passive"))
    )
    (net (code "38") (name "Net-(DS4-A)") (class "Default")
      (node (ref "DS4") (pin "1") (pinfunction "A_1") (pintype "passive"))
      (node (ref "R5") (pin "1") (pinfunction "1_1") (pintype "passive"))
    )
    (net (code "39") (name "Net-(DS4-K)") (class "Default")
      (node (ref "DS4") (pin "2") (pinfunction "K_2") (pintype "passive"))
      (node (ref "J2") (pin "4") (pinfunction "4_4") (pintype "passive"))
      (node (ref "U2") (pin "13") (pinfunction "4C_13") (pintype "passive"))
    )
    (net (code "40") (name "Net-(IC1-AVDD)") (class "Default")
      (node (ref "IC1") (pin "3") (pinfunction "AVDD_3") (pintype "passive"))
      (node (ref "L1") (pin "2") (pinfunction "2_2") (pintype "passive"))
      (node (ref "Q1") (pin "3") (pinfunction "C_3") (pintype "passive"))
      (node (ref "R8") (pin "1") (pinfunction "1_1") (pintype "passive"))
    )
    (net (code "41") (name "Net-(IC1-BASE)") (class "Default")
      (node (ref "IC1") (pin "2") (pinfunction "BASE_2") (pintype "passive"))
      (node (ref "Q1") (pin "1") (pinfunction "B_1") (pintype "passive"))
    )
    (net (code "42") (name "Net-(IC1-INNA)") (class "Default")
      (node (ref "C12") (pin "2") (pinfunction "2_2") (pintype "passive"))
      (node (ref "IC1") (pin "7") (pinfunction "INNA_7") (pintype "passive"))
      (node (ref "R13") (pin "2") (pinfunction "2_2") (pintype "passive"))
    )
    (net (code "43") (name "Net-(IC1-INPA)") (class "Default")
      (node (ref "C12") (pin "1") (pinfunction "1_1") (pintype "passive"))
      (node (ref "IC1") (pin "8") (pinfunction "INPA_8") (pintype "passive"))
      (node (ref "R14") (pin "2") (pinfunction "2_2") (pintype "passive"))
    )
    (net (code "44") (name "Net-(IC1-VBG)") (class "Default")
      (node (ref "C11") (pin "1") (pinfunction "1_1") (pintype "passive"))
      (node (ref "IC1") (pin "6") (pinfunction "VBG_6") (pintype "passive"))
    )
    (net (code "45") (name "Net-(IC1-VFB)") (class "Default")
      (node (ref "IC1") (pin "4") (pinfunction "VFB_4") (pintype "passive"))
      (node (ref "R11") (pin "2") (pinfunction "2_2") (pintype "passive"))
      (node (ref "R8") (pin "2") (pinfunction "2_2") (pintype "passive"))
    )
    (net (code "46") (name "Net-(J4-Pad3)") (class "Default")
      (node (ref "J4") (pin "3") (pinfunction "3_3") (pintype "passive"))
      (node (ref "R13") (pin "1") (pinfunction "1_1") (pintype "passive"))
    )
    (net (code "47") (name "Net-(J4-Pad4)") (class "Default")
      (node (ref "J4") (pin "4") (pinfunction "4_4") (pintype "passive"))
      (node (ref "R14") (pin "1") (pinfunction "1_1") (pintype "passive"))
    )
    (net (code "48") (name "Net-(LED1-A)") (class "Default")
      (node (ref "LED1") (pin "2") (pinfunction "A_2") (pintype "passive"))
      (node (ref "R10") (pin "1") (pinfunction "1_1") (pintype "passive"))
    )
    (net (code "49") (name "Net-(LED1-C)") (class "Default")
      (node (ref "LED1") (pin "1") (pinfunction "C_1") (pintype "passive"))
      (node (ref "U3") (pin "23") (pinfunction "CBUS0_23") (pintype "bidirectional"))
    )
    (net (code "50") (name "Net-(LED2-A)") (class "Default")
      (node (ref "LED2") (pin "2") (pinfunction "A_2") (pintype "passive"))
      (node (ref "R12") (pin "1") (pinfunction "1_1") (pintype "passive"))
    )
    (net (code "51") (name "Net-(LED2-C)") (class "Default")
      (node (ref "LED2") (pin "1") (pinfunction "C_1") (pintype "passive"))
      (node (ref "U3") (pin "22") (pinfunction "CBUS1_22") (pintype "bidirectional"))
    )
    (net (code "52") (name "Net-(U1-AREF)") (class "Default")
      (node (ref "C6") (pin "1") (pinfunction "1_1") (pintype "passive"))
      (node (ref "U1") (pin "20") (pinfunction "AREF_20") (pintype "passive"))
    )
    (net (code "53") (name "Net-(U1-PB6(TOSC1{slash}XTAL1{slash}PCINT6))") (class "Default")
      (node (ref "C8") (pin "1") (pinfunction "1_1") (pintype "passive"))
      (node (ref "U1") (pin "7") (pinfunction "PB6(TOSC1/XTAL1/PCINT6)_7") (pintype "bidirectional"))
      (node (ref "Y1") (pin "1") (pinfunction "CRYSTAL_1_1") (pintype "passive"))
    )
    (net (code "54") (name "Net-(U1-PB7(TOSC2{slash}XTAL2{slash}PCINT7))") (class "Default")
      (node (ref "C9") (pin "1") (pinfunction "1_1") (pintype "passive"))
      (node (ref "U1") (pin "8") (pinfunction "PB7(TOSC2/XTAL2/PCINT7)_8") (pintype "bidirectional"))
      (node (ref "Y1") (pin "3") (pinfunction "CRYSTAL_2_3") (pintype "passive"))
    )
    (net (code "55") (name "Net-(U1-PC6(~{RESET}{slash}PCINT14))") (class "Default")
      (node (ref "C7") (pin "1") (pinfunction "1_1") (pintype "passive"))
      (node (ref "J1") (pin "3") (pinfunction "3_3") (pintype "passive"))
      (node (ref "R1") (pin "2") (pinfunction "2_2") (pintype "passive"))
      (node (ref "U1") (pin "29") (pinfunction "PC6(~{RESET}/PCINT14)_29") (pintype "bidirectional"))
    )
    (net (code "56") (name "Net-(U3-3V3OUT)") (class "Default")
      (node (ref "C13") (pin "2") (pinfunction "2_2") (pintype "passive"))
      (node (ref "U3") (pin "17") (pinfunction "3V3OUT_17") (pintype "power_in"))
    )
    (net (code "57") (name "Net-(U3-RXD)") (class "Default")
      (node (ref "R7") (pin "1") (pinfunction "1_1") (pintype "passive"))
      (node (ref "U3") (pin "5") (pinfunction "RXD_5") (pintype "input"))
    )
    (net (code "58") (name "Net-(U3-TXD)") (class "Default")
      (node (ref "R6") (pin "1") (pinfunction "1_1") (pintype "passive"))
      (node (ref "U3") (pin "1") (pinfunction "TXD_1") (pintype "output"))
    )
    (net (code "59") (name "Net-(U4-Feedback)") (class "Default")
      (node (ref "R15") (pin "1") (pinfunction "1_1") (pintype "passive"))
      (node (ref "R16") (pin "2") (pinfunction "2_2") (pintype "passive"))
      (node (ref "U4") (pin "4") (pinfunction "Feedback_4") (pintype "passive"))
    )
    (net (code "60") (name "VCC") (class "Default")
      (node (ref "C19") (pin "2") (pinfunction "A_2") (pintype "passive"))
      (node (ref "D2") (pin "1") (pinfunction "C_1") (pintype "passive"))
      (node (ref "J13") (pin "1") (pinfunction "1_1") (pintype "passive"))
      (node (ref "U4") (pin "1") (pinfunction "Vin_1") (pintype "power_in"))
    )
    (net (code "61") (name "unconnected-(IC1-INNB-Pad9)") (class "Default")
      (node (ref "IC1") (pin "9") (pinfunction "INNB_9") (pintype "passive+no_connect"))
    )
    (net (code "62") (name "unconnected-(IC1-INPB-Pad10)") (class "Default")
      (node (ref "IC1") (pin "10") (pinfunction "INPB_10") (pintype "passive+no_connect"))
    )
    (net (code "63") (name "unconnected-(IC1-XO-Pad13)") (class "Default")
      (node (ref "IC1") (pin "13") (pinfunction "XO_13") (pintype "passive+no_connect"))
    )
    (net (code "64") (name "unconnected-(J3-Pad4)") (class "Default")
      (node (ref "J3") (pin "4") (pinfunction "4_4") (pintype "passive+no_connect"))
    )
    (net (code "65") (name "unconnected-(U1-ADC6-Pad19)") (class "Default")
      (node (ref "U1") (pin "19") (pinfunction "ADC6_19") (pintype "passive+no_connect"))
    )
    (net (code "66") (name "unconnected-(U1-ADC7-Pad22)") (class "Default")
      (node (ref "U1") (pin "22") (pinfunction "ADC7_22") (pintype "passive+no_connect"))
    )
    (net (code "67") (name "unconnected-(U2-5B-Pad5)") (class "Default")
      (node (ref "U2") (pin "5") (pinfunction "5B_5") (pintype "passive+no_connect"))
    )
    (net (code "68") (name "unconnected-(U2-5C-Pad12)") (class "Default")
      (node (ref "U2") (pin "12") (pinfunction "5C_12") (pintype "passive+no_connect"))
    )
    (net (code "69") (name "unconnected-(U2-6B-Pad6)") (class "Default")
      (node (ref "U2") (pin "6") (pinfunction "6B_6") (pintype "passive+no_connect"))
    )
    (net (code "70") (name "unconnected-(U2-6C-Pad11)") (class "Default")
      (node (ref "U2") (pin "11") (pinfunction "6C_11") (pintype "passive+no_connect"))
    )
    (net (code "71") (name "unconnected-(U2-7B-Pad7)") (class "Default")
      (node (ref "U2") (pin "7") (pinfunction "7B_7") (pintype "passive+no_connect"))
    )
    (net (code "72") (name "unconnected-(U2-7C-Pad10)") (class "Default")
      (node (ref "U2") (pin "10") (pinfunction "7C_10") (pintype "passive+no_connect"))
    )
    (net (code "73") (name "unconnected-(U3-CBUS2-Pad13)") (class "Default")
      (node (ref "U3") (pin "13") (pinfunction "CBUS2_13") (pintype "bidirectional+no_connect"))
    )
    (net (code "74") (name "unconnected-(U3-CBUS3-Pad14)") (class "Default")
      (node (ref "U3") (pin "14") (pinfunction "CBUS3_14") (pintype "bidirectional+no_connect"))
    )
    (net (code "75") (name "unconnected-(U3-CBUS4-Pad12)") (class "Default")
      (node (ref "U3") (pin "12") (pinfunction "CBUS4_12") (pintype "bidirectional+no_connect"))
    )
    (net (code "76") (name "unconnected-(U3-CTS#-Pad11)") (class "Default")
      (node (ref "U3") (pin "11") (pinfunction "CTS#_11") (pintype "input+no_connect"))
    )
    (net (code "77") (name "unconnected-(U3-DCD#-Pad10)") (class "Default")
      (node (ref "U3") (pin "10") (pinfunction "DCD#_10") (pintype "input+no_connect"))
    )
    (net (code "78") (name "unconnected-(U3-DSR#-Pad9)") (class "Default")
      (node (ref "U3") (pin "9") (pinfunction "DSR#_9") (pintype "input+no_connect"))
    )
    (net (code "79") (name "unconnected-(U3-NC-Pad8)") (class "Default")
      (node (ref "U3") (pin "8") (pinfunction "NC_8") (pintype "passive+no_connect"))
    )
    (net (code "80") (name "unconnected-(U3-NC-Pad24)") (class "Default")
      (node (ref "U3") (pin "24") (pinfunction "NC_24") (pintype "passive+no_connect"))
    )
    (net (code "81") (name "unconnected-(U3-OSCI-Pad27)") (class "Default")
      (node (ref "U3") (pin "27") (pinfunction "OSCI_27") (pintype "input+no_connect"))
    )
    (net (code "82") (name "unconnected-(U3-OSCO-Pad28)") (class "Default")
      (node (ref "U3") (pin "28") (pinfunction "OSCO_28") (pintype "output+no_connect"))
    )
    (net (code "83") (name "unconnected-(U3-RESET#-Pad19)") (class "Default")
      (node (ref "U3") (pin "19") (pinfunction "RESET#_19") (pintype "input+no_connect"))
    )
    (net (code "84") (name "unconnected-(U3-RI#-Pad6)") (class "Default")
      (node (ref "U3") (pin "6") (pinfunction "RI#_6") (pintype "input+no_connect"))
    )
    (net (code "85") (name "unconnected-(U3-RTS#-Pad3)") (class "Default")
      (node (ref "U3") (pin "3") (pinfunction "RTS#_3") (pintype "output"))
    )
  )
)
